# DDC118_eval2_rev1E.net
KiCad netlist of a schematic drawn in EAGLE
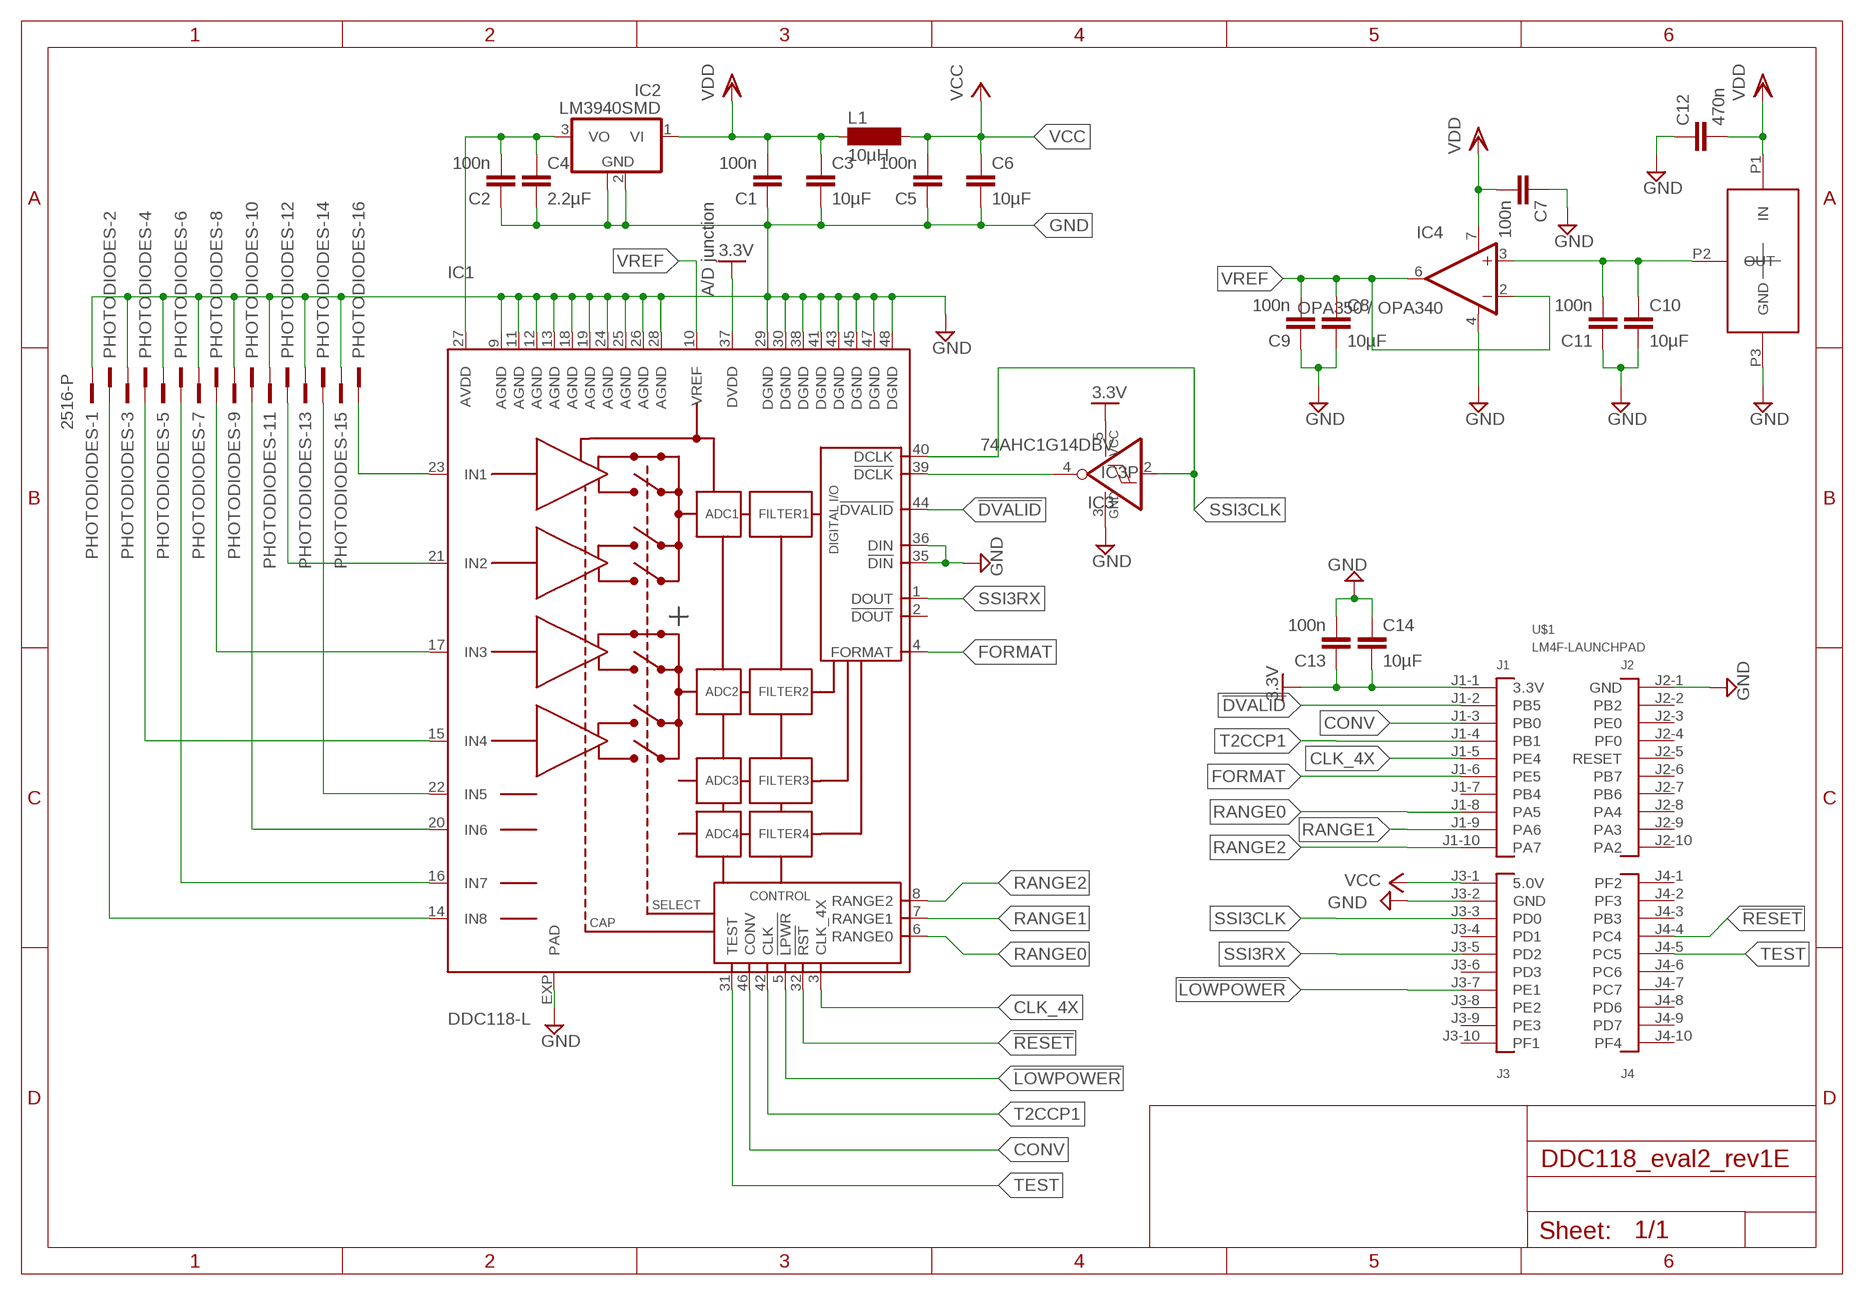
[diagram p0: schematic, sheet 1]

(export (version "E")
  (design (tool "Eeschema 10.0.6"))
  (components
    (comp (ref "C1")
      (value "100n")
      (footprint "eagle-import:C0805K")
      (libsource (lib "eagle-import") (part "C-EUC0805K"))
    )
    (comp (ref "C2")
      (value "100n")
      (footprint "eagle-import:C0805K")
      (libsource (lib "eagle-import") (part "C-EUC0805K"))
    )
    (comp (ref "C3")
      (value "10µF")
      (footprint "eagle-import:C0805")
      (libsource (lib "eagle-import") (part "C-EUC0805"))
    )
    (comp (ref "C4")
      (value "2.2µF")
      (footprint "eagle-import:C0805")
      (libsource (lib "eagle-import") (part "C-EUC0805"))
    )
    (comp (ref "C5")
      (value "100n")
      (footprint "eagle-import:C0805K")
      (libsource (lib "eagle-import") (part "C-EUC0805K"))
    )
    (comp (ref "C6")
      (value "10µF")
      (footprint "eagle-import:C0805")
      (libsource (lib "eagle-import") (part "C-EUC0805"))
    )
    (comp (ref "C7")
      (value "100n")
      (footprint "eagle-import:C0805K")
      (libsource (lib "eagle-import") (part "C-EUC0805K"))
    )
    (comp (ref "C8")
      (value "10µF")
      (footprint "eagle-import:C0805")
      (libsource (lib "eagle-import") (part "C-EUC0805"))
    )
    (comp (ref "C9")
      (value "100n")
      (footprint "eagle-import:C0805K")
      (libsource (lib "eagle-import") (part "C-EUC0805K"))
    )
    (comp (ref "C10")
      (value "10µF")
      (footprint "eagle-import:C0805")
      (libsource (lib "eagle-import") (part "C-EUC0805"))
    )
    (comp (ref "C11")
      (value "100n")
      (footprint "eagle-import:C0805K")
      (libsource (lib "eagle-import") (part "C-EUC0805K"))
    )
    (comp (ref "C12")
      (value "470n")
      (footprint "eagle-import:C0805K")
      (libsource (lib "eagle-import") (part "C-EUC0805K"))
    )
    (comp (ref "C13")
      (value "100n")
      (footprint "eagle-import:C0805K")
      (libsource (lib "eagle-import") (part "C-EUC0805K"))
    )
    (comp (ref "C14")
      (value "10µF")
      (footprint "eagle-import:C0805")
      (libsource (lib "eagle-import") (part "C-EUC0805"))
    )
    (comp (ref "IC1")
      (value "DDC118-L")
      (footprint "eagle-import:VQFN48-L")
      (libsource (lib "eagle-import") (part "DDC118-L"))
    )
    (comp (ref "IC2")
      (value "LM3940SMD")
      (footprint "eagle-import:SOT223")
      (libsource (lib "eagle-import") (part "LM3940SMD"))
    )
    (comp (ref "IC3")
      (value "74AHC1G14DBV")
      (footprint "eagle-import:SOT23-5")
      (libsource (lib "eagle-import") (part "741G14DBVAHC"))
    )
    (comp (ref "IC4")
      (value "OPA350 / OPA340")
      (footprint "eagle-import:SO08")
      (fields (field (name "MPN") "OPA340UA"))
      (libsource (lib "eagle-import") (part "OPA340U"))
    )
    (comp (ref "L1")
      (value "10µH")
      (footprint "eagle-import:MS50")
      (libsource (lib "eagle-import") (part "MS50"))
    )
    (comp (ref "PHOTODIODES")
      (value "2516-P")
      (footprint "eagle-import:PAK100_2500-16-PADS")
      (libsource (lib "eagle-import") (part "2516-P"))
    )
    (comp (ref "U$1")
      (value "LM4F-LAUNCHPAD")
      (footprint "eagle-import:LM4F120-LAUNCHPAD")
      (libsource (lib "eagle-import") (part "LM4F-LAUNCHPAD"))
    )
    (comp (ref "U1")
      (value "REF30XX")
      (footprint "eagle-import:SOT-23")
      (libsource (lib "eagle-import") (part "REF30XX"))
    )
  )
  (nets
    (net (code "1") (name "/PF2") (class "Default")
      (node (ref "U$1") (pin "J4-1") (pinfunction "PF2_J4-1") (pintype "power_in"))
    )
    (net (code "2") (name "/~{DVALID}") (class "Default")
      (node (ref "IC1") (pin "44") (pinfunction "~{DVALID}_44") (pintype "output"))
      (node (ref "U$1") (pin "J1-2") (pinfunction "PB5_J1-2") (pintype "bidirectional"))
    )
    (net (code "3") (name "/~{LOWPOWER}") (class "Default")
      (node (ref "IC1") (pin "5") (pinfunction "~{LPWR}_5") (pintype "input"))
      (node (ref "U$1") (pin "J3-7") (pinfunction "PE1_J3-7") (pintype "bidirectional"))
    )
    (net (code "4") (name "/~{RESET}") (class "Default")
      (node (ref "IC1") (pin "32") (pinfunction "~{RST}_32") (pintype "input"))
      (node (ref "U$1") (pin "J4-4") (pinfunction "PC4_J4-4") (pintype "bidirectional"))
    )
    (net (code "5") (name "3.3V") (class "Default")
      (node (ref "C13") (pin "1") (pinfunction "1_1") (pintype "passive"))
      (node (ref "C14") (pin "2") (pinfunction "2_2") (pintype "passive"))
      (node (ref "IC1") (pin "37") (pinfunction "DVDD_37") (pintype "power_in"))
      (node (ref "IC3") (pin "5") (pinfunction "VCC_5") (pintype "power_in"))
      (node (ref "U$1") (pin "J1-1") (pinfunction "3.3V_J1-1") (pintype "power_in"))
    )
    (net (code "6") (name "CLK_4X") (class "Default")
      (node (ref "IC1") (pin "3") (pinfunction "CLK_4X_3") (pintype "input"))
      (node (ref "U$1") (pin "J1-5") (pinfunction "PE4_J1-5") (pintype "bidirectional"))
    )
    (net (code "7") (name "CONV") (class "Default")
      (node (ref "IC1") (pin "46") (pinfunction "CONV_46") (pintype "input"))
      (node (ref "U$1") (pin "J1-3") (pinfunction "PB0_J1-3") (pintype "bidirectional"))
    )
    (net (code "8") (name "FORMAT") (class "Default")
      (node (ref "IC1") (pin "4") (pinfunction "FORMAT_4") (pintype "output"))
      (node (ref "U$1") (pin "J1-6") (pinfunction "PE5_J1-6") (pintype "bidirectional"))
    )
    (net (code "9") (name "GND") (class "Default")
      (node (ref "C1") (pin "1") (pinfunction "1_1") (pintype "passive"))
      (node (ref "C10") (pin "2") (pinfunction "2_2") (pintype "passive"))
      (node (ref "C11") (pin "1") (pinfunction "1_1") (pintype "passive"))
      (node (ref "C12") (pin "1") (pinfunction "1_1") (pintype "passive"))
      (node (ref "C13") (pin "2") (pinfunction "2_2") (pintype "passive"))
      (node (ref "C14") (pin "1") (pinfunction "1_1") (pintype "passive"))
      (node (ref "C2") (pin "1") (pinfunction "1_1") (pintype "passive"))
      (node (ref "C3") (pin "2") (pinfunction "2_2") (pintype "passive"))
      (node (ref "C4") (pin "2") (pinfunction "2_2") (pintype "passive"))
      (node (ref "C5") (pin "1") (pinfunction "1_1") (pintype "passive"))
      (node (ref "C6") (pin "2") (pinfunction "2_2") (pintype "passive"))
      (node (ref "C7") (pin "1") (pinfunction "1_1") (pintype "passive"))
      (node (ref "C8") (pin "2") (pinfunction "2_2") (pintype "passive"))
      (node (ref "C9") (pin "1") (pinfunction "1_1") (pintype "passive"))
      (node (ref "IC1") (pin "11") (pinfunction "AGND_11") (pintype "power_in"))
      (node (ref "IC1") (pin "12") (pinfunction "AGND_12") (pintype "power_in"))
      (node (ref "IC1") (pin "13") (pinfunction "AGND_13") (pintype "power_in"))
      (node (ref "IC1") (pin "18") (pinfunction "AGND_18") (pintype "power_in"))
      (node (ref "IC1") (pin "19") (pinfunction "AGND_19") (pintype "power_in"))
      (node (ref "IC1") (pin "24") (pinfunction "AGND_24") (pintype "power_in"))
      (node (ref "IC1") (pin "25") (pinfunction "AGND_25") (pintype "power_in"))
      (node (ref "IC1") (pin "26") (pinfunction "AGND_26") (pintype "power_in"))
      (node (ref "IC1") (pin "28") (pinfunction "AGND_28") (pintype "power_in"))
      (node (ref "IC1") (pin "29") (pinfunction "DGND_29") (pintype "power_in"))
      (node (ref "IC1") (pin "30") (pinfunction "DGND_30") (pintype "power_in"))
      (node (ref "IC1") (pin "35") (pinfunction "~{DIN}_35") (pintype "input"))
      (node (ref "IC1") (pin "36") (pinfunction "DIN_36") (pintype "input"))
      (node (ref "IC1") (pin "38") (pinfunction "DGND_38") (pintype "power_in"))
      (node (ref "IC1") (pin "41") (pinfunction "DGND_41") (pintype "power_in"))
      (node (ref "IC1") (pin "43") (pinfunction "DGND_43") (pintype "power_in"))
      (node (ref "IC1") (pin "45") (pinfunction "DGND_45") (pintype "power_in"))
      (node (ref "IC1") (pin "47") (pinfunction "DGND_47") (pintype "power_in"))
      (node (ref "IC1") (pin "48") (pinfunction "DGND_48") (pintype "power_in"))
      (node (ref "IC1") (pin "9") (pinfunction "AGND_9") (pintype "power_in"))
      (node (ref "IC1") (pin "EXP") (pinfunction "PAD_EXP") (pintype "power_in"))
      (node (ref "IC2") (pin "2") (pinfunction "GND_2") (pintype "passive"))
      (node (ref "IC2") (pin "4") (pinfunction "GND_4") (pintype "passive"))
      (node (ref "IC3") (pin "3") (pinfunction "GND_3") (pintype "power_in"))
      (node (ref "IC4") (pin "4") (pinfunction "V-_4") (pintype "power_in"))
      (node (ref "PHOTODIODES") (pin "1") (pinfunction "KL_1") (pintype "passive"))
      (node (ref "PHOTODIODES") (pin "11") (pinfunction "KL_11") (pintype "passive"))
      (node (ref "PHOTODIODES") (pin "13") (pinfunction "KL_13") (pintype "passive"))
      (node (ref "PHOTODIODES") (pin "15") (pinfunction "KL_15") (pintype "passive"))
      (node (ref "PHOTODIODES") (pin "3") (pinfunction "KL_3") (pintype "passive"))
      (node (ref "PHOTODIODES") (pin "5") (pinfunction "KL_5") (pintype "passive"))
      (node (ref "PHOTODIODES") (pin "7") (pinfunction "KL_7") (pintype "passive"))
      (node (ref "PHOTODIODES") (pin "9") (pinfunction "KL_9") (pintype "passive"))
      (node (ref "U$1") (pin "J2-1") (pinfunction "GND_J2-1") (pintype "power_in"))
      (node (ref "U$1") (pin "J3-2") (pinfunction "GND_J3-2") (pintype "bidirectional"))
      (node (ref "U1") (pin "P3") (pinfunction "GND_P3") (pintype "bidirectional"))
    )
    (net (code "10") (name "Net-(IC1-AVDD)") (class "Default")
      (node (ref "C2") (pin "2") (pinfunction "2_2") (pintype "passive"))
      (node (ref "C4") (pin "1") (pinfunction "1_1") (pintype "passive"))
      (node (ref "IC1") (pin "27") (pinfunction "AVDD_27") (pintype "power_in"))
      (node (ref "IC2") (pin "3") (pinfunction "VO_3") (pintype "passive"))
    )
    (net (code "11") (name "Net-(IC1-IN1)") (class "Default")
      (node (ref "IC1") (pin "23") (pinfunction "IN1_23") (pintype "input"))
      (node (ref "PHOTODIODES") (pin "16") (pinfunction "KL_16") (pintype "passive"))
    )
    (net (code "12") (name "Net-(IC1-IN2)") (class "Default")
      (node (ref "IC1") (pin "21") (pinfunction "IN2_21") (pintype "input"))
      (node (ref "PHOTODIODES") (pin "12") (pinfunction "KL_12") (pintype "passive"))
    )
    (net (code "13") (name "Net-(IC1-IN3)") (class "Default")
      (node (ref "IC1") (pin "17") (pinfunction "IN3_17") (pintype "input"))
      (node (ref "PHOTODIODES") (pin "8") (pinfunction "KL_8") (pintype "passive"))
    )
    (net (code "14") (name "Net-(IC1-IN4)") (class "Default")
      (node (ref "IC1") (pin "15") (pinfunction "IN4_15") (pintype "input"))
      (node (ref "PHOTODIODES") (pin "4") (pinfunction "KL_4") (pintype "passive"))
    )
    (net (code "15") (name "Net-(IC1-IN5)") (class "Default")
      (node (ref "IC1") (pin "22") (pinfunction "IN5_22") (pintype "input"))
      (node (ref "PHOTODIODES") (pin "14") (pinfunction "KL_14") (pintype "passive"))
    )
    (net (code "16") (name "Net-(IC1-IN6)") (class "Default")
      (node (ref "IC1") (pin "20") (pinfunction "IN6_20") (pintype "input"))
      (node (ref "PHOTODIODES") (pin "10") (pinfunction "KL_10") (pintype "passive"))
    )
    (net (code "17") (name "Net-(IC1-IN7)") (class "Default")
      (node (ref "IC1") (pin "16") (pinfunction "IN7_16") (pintype "input"))
      (node (ref "PHOTODIODES") (pin "6") (pinfunction "KL_6") (pintype "passive"))
    )
    (net (code "18") (name "Net-(IC1-IN8)") (class "Default")
      (node (ref "IC1") (pin "14") (pinfunction "IN8_14") (pintype "input"))
      (node (ref "PHOTODIODES") (pin "2") (pinfunction "KL_2") (pintype "passive"))
    )
    (net (code "19") (name "Net-(IC1-~{DCLK})") (class "Default")
      (node (ref "IC1") (pin "39") (pinfunction "~{DCLK}_39") (pintype "input"))
      (node (ref "IC3") (pin "4") (pinfunction "O_4") (pintype "output"))
    )
    (net (code "20") (name "Net-(IC4-+IN)") (class "Default")
      (node (ref "C10") (pin "1") (pinfunction "1_1") (pintype "passive"))
      (node (ref "C11") (pin "2") (pinfunction "2_2") (pintype "passive"))
      (node (ref "IC4") (pin "3") (pinfunction "+IN_3") (pintype "input"))
      (node (ref "U1") (pin "P2") (pinfunction "OUT_P2") (pintype "bidirectional"))
    )
    (net (code "21") (name "RANGE0") (class "Default")
      (node (ref "IC1") (pin "6") (pinfunction "RANGE0_6") (pintype "output"))
      (node (ref "U$1") (pin "J1-8") (pinfunction "PA5_J1-8") (pintype "bidirectional"))
    )
    (net (code "22") (name "RANGE1") (class "Default")
      (node (ref "IC1") (pin "7") (pinfunction "RANGE1_7") (pintype "output"))
      (node (ref "U$1") (pin "J1-9") (pinfunction "PA6_J1-9") (pintype "bidirectional"))
    )
    (net (code "23") (name "RANGE2") (class "Default")
      (node (ref "IC1") (pin "8") (pinfunction "RANGE2_8") (pintype "output"))
      (node (ref "U$1") (pin "J1-10") (pinfunction "PA7_J1-10") (pintype "bidirectional"))
    )
    (net (code "24") (name "SSI3CLK") (class "Default")
      (node (ref "IC1") (pin "40") (pinfunction "DCLK_40") (pintype "input"))
      (node (ref "IC3") (pin "2") (pinfunction "I_2") (pintype "input"))
      (node (ref "U$1") (pin "J3-3") (pinfunction "PD0_J3-3") (pintype "bidirectional"))
    )
    (net (code "25") (name "SSI3RX") (class "Default")
      (node (ref "IC1") (pin "1") (pinfunction "DOUT_1") (pintype "output"))
      (node (ref "U$1") (pin "J3-5") (pinfunction "PD2_J3-5") (pintype "bidirectional"))
    )
    (net (code "26") (name "T2CCP1") (class "Default")
      (node (ref "IC1") (pin "42") (pinfunction "CLK_42") (pintype "input"))
      (node (ref "U$1") (pin "J1-4") (pinfunction "PB1_J1-4") (pintype "bidirectional"))
    )
    (net (code "27") (name "TEST") (class "Default")
      (node (ref "IC1") (pin "31") (pinfunction "TEST_31") (pintype "power_in"))
      (node (ref "U$1") (pin "J4-5") (pinfunction "PC5_J4-5") (pintype "bidirectional"))
    )
    (net (code "28") (name "VCC") (class "Default")
      (node (ref "C5") (pin "2") (pinfunction "2_2") (pintype "passive"))
      (node (ref "C6") (pin "1") (pinfunction "1_1") (pintype "passive"))
      (node (ref "L1") (pin "2") (pinfunction "2_2") (pintype "passive"))
      (node (ref "U$1") (pin "J3-1") (pinfunction "5.0V_J3-1") (pintype "power_in"))
    )
    (net (code "29") (name "VDD") (class "Default")
      (node (ref "C1") (pin "2") (pinfunction "2_2") (pintype "passive"))
      (node (ref "C12") (pin "2") (pinfunction "2_2") (pintype "passive"))
      (node (ref "C3") (pin "1") (pinfunction "1_1") (pintype "passive"))
      (node (ref "C7") (pin "2") (pinfunction "2_2") (pintype "passive"))
      (node (ref "IC2") (pin "1") (pinfunction "VI_1") (pintype "input"))
      (node (ref "IC4") (pin "7") (pinfunction "V+_7") (pintype "power_in"))
      (node (ref "L1") (pin "1") (pinfunction "1_1") (pintype "passive"))
      (node (ref "U1") (pin "P1") (pinfunction "IN_P1") (pintype "bidirectional"))
    )
    (net (code "30") (name "VREF") (class "Default")
      (node (ref "C8") (pin "1") (pinfunction "1_1") (pintype "passive"))
      (node (ref "C9") (pin "2") (pinfunction "2_2") (pintype "passive"))
      (node (ref "IC1") (pin "10") (pinfunction "VREF_10") (pintype "passive"))
      (node (ref "IC4") (pin "2") (pinfunction "-IN_2") (pintype "input"))
      (node (ref "IC4") (pin "6") (pinfunction "OUT_6") (pintype "output"))
    )
    (net (code "31") (name "unconnected-(IC1-~{DOUT}-Pad2)") (class "Default")
      (node (ref "IC1") (pin "2") (pinfunction "~{DOUT}_2") (pintype "output"))
    )
    (net (code "32") (name "unconnected-(U$1-PA2-PadJ2-10)") (class "Default")
      (node (ref "U$1") (pin "J2-10") (pinfunction "PA2_J2-10") (pintype "bidirectional"))
    )
    (net (code "33") (name "unconnected-(U$1-PA3-PadJ2-9)") (class "Default")
      (node (ref "U$1") (pin "J2-9") (pinfunction "PA3_J2-9") (pintype "bidirectional"))
    )
    (net (code "34") (name "unconnected-(U$1-PA4-PadJ2-8)") (class "Default")
      (node (ref "U$1") (pin "J2-8") (pinfunction "PA4_J2-8") (pintype "bidirectional"))
    )
    (net (code "35") (name "unconnected-(U$1-PB2-PadJ2-2)") (class "Default")
      (node (ref "U$1") (pin "J2-2") (pinfunction "PB2_J2-2") (pintype "bidirectional"))
    )
    (net (code "36") (name "unconnected-(U$1-PB3-PadJ4-3)") (class "Default")
      (node (ref "U$1") (pin "J4-3") (pinfunction "PB3_J4-3") (pintype "bidirectional"))
    )
    (net (code "37") (name "unconnected-(U$1-PB4-PadJ1-7)") (class "Default")
      (node (ref "U$1") (pin "J1-7") (pinfunction "PB4_J1-7") (pintype "bidirectional"))
    )
    (net (code "38") (name "unconnected-(U$1-PB6-PadJ2-7)") (class "Default")
      (node (ref "U$1") (pin "J2-7") (pinfunction "PB6_J2-7") (pintype "bidirectional"))
    )
    (net (code "39") (name "unconnected-(U$1-PB7-PadJ2-6)") (class "Default")
      (node (ref "U$1") (pin "J2-6") (pinfunction "PB7_J2-6") (pintype "bidirectional"))
    )
    (net (code "40") (name "unconnected-(U$1-PC6-PadJ4-6)") (class "Default")
      (node (ref "U$1") (pin "J4-6") (pinfunction "PC6_J4-6") (pintype "bidirectional"))
    )
    (net (code "41") (name "unconnected-(U$1-PC7-PadJ4-7)") (class "Default")
      (node (ref "U$1") (pin "J4-7") (pinfunction "PC7_J4-7") (pintype "bidirectional"))
    )
    (net (code "42") (name "unconnected-(U$1-PD1-PadJ3-4)") (class "Default")
      (node (ref "U$1") (pin "J3-4") (pinfunction "PD1_J3-4") (pintype "bidirectional"))
    )
    (net (code "43") (name "unconnected-(U$1-PD3-PadJ3-6)") (class "Default")
      (node (ref "U$1") (pin "J3-6") (pinfunction "PD3_J3-6") (pintype "bidirectional"))
    )
    (net (code "44") (name "unconnected-(U$1-PD6-PadJ4-8)") (class "Default")
      (node (ref "U$1") (pin "J4-8") (pinfunction "PD6_J4-8") (pintype "bidirectional"))
    )
    (net (code "45") (name "unconnected-(U$1-PD7-PadJ4-9)") (class "Default")
      (node (ref "U$1") (pin "J4-9") (pinfunction "PD7_J4-9") (pintype "bidirectional"))
    )
    (net (code "46") (name "unconnected-(U$1-PE0-PadJ2-3)") (class "Default")
      (node (ref "U$1") (pin "J2-3") (pinfunction "PE0_J2-3") (pintype "bidirectional"))
    )
    (net (code "47") (name "unconnected-(U$1-PE2-PadJ3-8)") (class "Default")
      (node (ref "U$1") (pin "J3-8") (pinfunction "PE2_J3-8") (pintype "bidirectional"))
    )
    (net (code "48") (name "unconnected-(U$1-PE3-PadJ3-9)") (class "Default")
      (node (ref "U$1") (pin "J3-9") (pinfunction "PE3_J3-9") (pintype "bidirectional"))
    )
    (net (code "49") (name "unconnected-(U$1-PF0-PadJ2-4)") (class "Default")
      (node (ref "U$1") (pin "J2-4") (pinfunction "PF0_J2-4") (pintype "bidirectional"))
    )
    (net (code "50") (name "unconnected-(U$1-PF1-PadJ3-10)") (class "Default")
      (node (ref "U$1") (pin "J3-10") (pinfunction "PF1_J3-10") (pintype "bidirectional"))
    )
    (net (code "51") (name "unconnected-(U$1-PF3-PadJ4-2)") (class "Default")
      (node (ref "U$1") (pin "J4-2") (pinfunction "PF3_J4-2") (pintype "bidirectional"))
    )
    (net (code "52") (name "unconnected-(U$1-PF4-PadJ4-10)") (class "Default")
      (node (ref "U$1") (pin "J4-10") (pinfunction "PF4_J4-10") (pintype "bidirectional"))
    )
    (net (code "53") (name "unconnected-(U$1-RESET-PadJ2-5)") (class "Default")
      (node (ref "U$1") (pin "J2-5") (pinfunction "RESET_J2-5") (pintype "bidirectional"))
    )
  )
)
